# MAGI_sDIPBoard-2x.net
KiCad netlist of a schematic drawn in Altium Designer
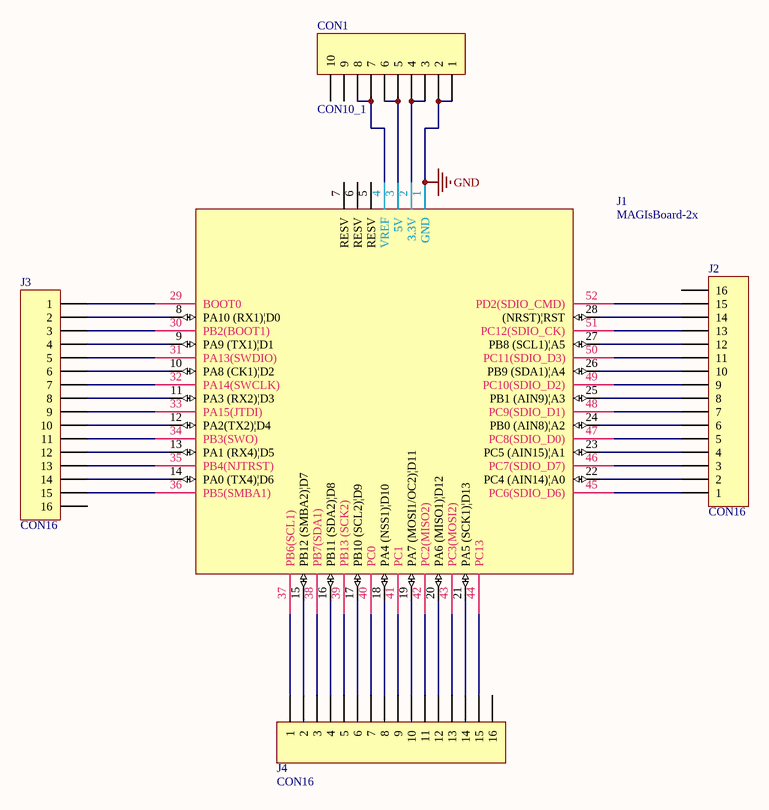
[diagram p0: MAGI'sDIPBoard-2x.SchDoc]

(export (version "E")
  (design (tool "Eeschema 10.0.6"))
  (components
    (comp (ref "CON1")
      (value "CON10_1")
      (footprint "idc10")
      (description "Connector")
      (libsource (lib "CON系列") (part "CON10_1"))
    )
    (comp (ref "J1")
      (value "MAGIsBoard-2x")
      (footprint "MAGIsBoard-2x")
      (libsource (lib "MAGIsBoard") (part "MAGIsBoard-2x"))
    )
    (comp (ref "J2")
      (value "CON16")
      (footprint "idc16")
      (description "Connector")
      (libsource (lib "") (part "CON16_2"))
    )
    (comp (ref "J3")
      (value "CON16")
      (footprint "idc16")
      (description "Connector")
      (libsource (lib "CON系列") (part "CON16"))
    )
    (comp (ref "J4")
      (value "CON16")
      (footprint "idc16")
      (description "Connector")
      (libsource (lib "") (part "CON16_1"))
    )
  )
  (nets
    (net (code "1") (name "GND") (class "Default")
      (node (ref "CON1") (pin "1") (pinfunction "1_1") (pintype "passive"))
      (node (ref "CON1") (pin "2") (pinfunction "2_2") (pintype "passive"))
      (node (ref "J1") (pin "1") (pinfunction "GND_1") (pintype "power_in"))
    )
    (net (code "2") (name "Net-(J1-(NRST)¦RST)") (class "Default")
      (node (ref "J1") (pin "28") (pinfunction "(NRST)¦RST_28") (pintype "bidirectional"))
      (node (ref "J2") (pin "14") (pinfunction "14_14") (pintype "passive"))
    )
    (net (code "3") (name "Net-(J1-3.3V)") (class "Default")
      (node (ref "CON1") (pin "3") (pinfunction "3_3") (pintype "passive"))
      (node (ref "CON1") (pin "4") (pinfunction "4_4") (pintype "passive"))
      (node (ref "J1") (pin "2") (pinfunction "3.3V_2") (pintype "power_in"))
    )
    (net (code "4") (name "Net-(J1-5V)") (class "Default")
      (node (ref "CON1") (pin "5") (pinfunction "5_5") (pintype "passive"))
      (node (ref "CON1") (pin "6") (pinfunction "6_6") (pintype "passive"))
      (node (ref "J1") (pin "3") (pinfunction "5V_3") (pintype "power_in"))
    )
    (net (code "5") (name "Net-(J1-BOOT0)") (class "Default")
      (node (ref "J1") (pin "29") (pinfunction "BOOT0_29") (pintype "passive"))
      (node (ref "J3") (pin "1") (pinfunction "1_1") (pintype "passive"))
    )
    (net (code "6") (name "Net-(J1-PA0_(TX4)¦D6)") (class "Default")
      (node (ref "J1") (pin "14") (pinfunction "PA0_(TX4)¦D6_14") (pintype "bidirectional"))
      (node (ref "J3") (pin "14") (pinfunction "14_14") (pintype "passive"))
    )
    (net (code "7") (name "Net-(J1-PA1_(RX4)¦D5)") (class "Default")
      (node (ref "J1") (pin "13") (pinfunction "PA1_(RX4)¦D5_13") (pintype "bidirectional"))
      (node (ref "J3") (pin "12") (pinfunction "12_12") (pintype "passive"))
    )
    (net (code "8") (name "Net-(J1-PA2(TX2)¦D4)") (class "Default")
      (node (ref "J1") (pin "12") (pinfunction "PA2(TX2)¦D4_12") (pintype "bidirectional"))
      (node (ref "J3") (pin "10") (pinfunction "10_10") (pintype "passive"))
    )
    (net (code "9") (name "Net-(J1-PA3_(RX2)¦D3)") (class "Default")
      (node (ref "J1") (pin "11") (pinfunction "PA3_(RX2)¦D3_11") (pintype "bidirectional"))
      (node (ref "J3") (pin "8") (pinfunction "8_8") (pintype "passive"))
    )
    (net (code "10") (name "Net-(J1-PA4_(NSS1)¦D10)") (class "Default")
      (node (ref "J1") (pin "18") (pinfunction "PA4_(NSS1)¦D10_18") (pintype "bidirectional"))
      (node (ref "J4") (pin "8") (pinfunction "8_8") (pintype "passive"))
    )
    (net (code "11") (name "Net-(J1-PA5_(SCK1)¦D13)") (class "Default")
      (node (ref "J1") (pin "21") (pinfunction "PA5_(SCK1)¦D13_21") (pintype "bidirectional"))
      (node (ref "J4") (pin "14") (pinfunction "14_14") (pintype "passive"))
    )
    (net (code "12") (name "Net-(J1-PA6_(MISO1)¦D12)") (class "Default")
      (node (ref "J1") (pin "20") (pinfunction "PA6_(MISO1)¦D12_20") (pintype "bidirectional"))
      (node (ref "J4") (pin "12") (pinfunction "12_12") (pintype "passive"))
    )
    (net (code "13") (name "Net-(J1-PA7_(MOSI1{slash}OC2)¦D11)") (class "Default")
      (node (ref "J1") (pin "19") (pinfunction "PA7_(MOSI1/OC2)¦D11_19") (pintype "bidirectional"))
      (node (ref "J4") (pin "10") (pinfunction "10_10") (pintype "passive"))
    )
    (net (code "14") (name "Net-(J1-PA8_(CK1)¦D2)") (class "Default")
      (node (ref "J1") (pin "10") (pinfunction "PA8_(CK1)¦D2_10") (pintype "bidirectional"))
      (node (ref "J3") (pin "6") (pinfunction "6_6") (pintype "passive"))
    )
    (net (code "15") (name "Net-(J1-PA9_(TX1)¦D1)") (class "Default")
      (node (ref "J1") (pin "9") (pinfunction "PA9_(TX1)¦D1_9") (pintype "bidirectional"))
      (node (ref "J3") (pin "4") (pinfunction "4_4") (pintype "passive"))
    )
    (net (code "16") (name "Net-(J1-PA10_(RX1)¦D0)") (class "Default")
      (node (ref "J1") (pin "8") (pinfunction "PA10_(RX1)¦D0_8") (pintype "bidirectional"))
      (node (ref "J3") (pin "2") (pinfunction "2_2") (pintype "passive"))
    )
    (net (code "17") (name "Net-(J1-PA13(SWDIO))") (class "Default")
      (node (ref "J1") (pin "31") (pinfunction "PA13(SWDIO)_31") (pintype "passive"))
      (node (ref "J3") (pin "5") (pinfunction "5_5") (pintype "passive"))
    )
    (net (code "18") (name "Net-(J1-PA14(SWCLK))") (class "Default")
      (node (ref "J1") (pin "32") (pinfunction "PA14(SWCLK)_32") (pintype "passive"))
      (node (ref "J3") (pin "7") (pinfunction "7_7") (pintype "passive"))
    )
    (net (code "19") (name "Net-(J1-PA15(JTDI))") (class "Default")
      (node (ref "J1") (pin "33") (pinfunction "PA15(JTDI)_33") (pintype "passive"))
      (node (ref "J3") (pin "9") (pinfunction "9_9") (pintype "passive"))
    )
    (net (code "20") (name "Net-(J1-PB0_(AIN8)¦A2)") (class "Default")
      (node (ref "J1") (pin "24") (pinfunction "PB0_(AIN8)¦A2_24") (pintype "bidirectional"))
      (node (ref "J2") (pin "6") (pinfunction "6_6") (pintype "passive"))
    )
    (net (code "21") (name "Net-(J1-PB1_(AIN9)¦A3)") (class "Default")
      (node (ref "J1") (pin "25") (pinfunction "PB1_(AIN9)¦A3_25") (pintype "bidirectional"))
      (node (ref "J2") (pin "8") (pinfunction "8_8") (pintype "passive"))
    )
    (net (code "22") (name "Net-(J1-PB2(BOOT1))") (class "Default")
      (node (ref "J1") (pin "30") (pinfunction "PB2(BOOT1)_30") (pintype "passive"))
      (node (ref "J3") (pin "3") (pinfunction "3_3") (pintype "passive"))
    )
    (net (code "23") (name "Net-(J1-PB3(SWO))") (class "Default")
      (node (ref "J1") (pin "34") (pinfunction "PB3(SWO)_34") (pintype "passive"))
      (node (ref "J3") (pin "11") (pinfunction "11_11") (pintype "passive"))
    )
    (net (code "24") (name "Net-(J1-PB4(NJTRST))") (class "Default")
      (node (ref "J1") (pin "35") (pinfunction "PB4(NJTRST)_35") (pintype "passive"))
      (node (ref "J3") (pin "13") (pinfunction "13_13") (pintype "passive"))
    )
    (net (code "25") (name "Net-(J1-PB5(SMBA1))") (class "Default")
      (node (ref "J1") (pin "36") (pinfunction "PB5(SMBA1)_36") (pintype "passive"))
      (node (ref "J3") (pin "15") (pinfunction "15_15") (pintype "passive"))
    )
    (net (code "26") (name "Net-(J1-PB6(SCL1))") (class "Default")
      (node (ref "J1") (pin "37") (pinfunction "PB6(SCL1)_37") (pintype "passive"))
      (node (ref "J4") (pin "1") (pinfunction "1_1") (pintype "passive"))
    )
    (net (code "27") (name "Net-(J1-PB7(SDA1))") (class "Default")
      (node (ref "J1") (pin "38") (pinfunction "PB7(SDA1)_38") (pintype "passive"))
      (node (ref "J4") (pin "3") (pinfunction "3_3") (pintype "passive"))
    )
    (net (code "28") (name "Net-(J1-PB8_(SCL1)¦A5)") (class "Default")
      (node (ref "J1") (pin "27") (pinfunction "PB8_(SCL1)¦A5_27") (pintype "bidirectional"))
      (node (ref "J2") (pin "12") (pinfunction "12_12") (pintype "passive"))
    )
    (net (code "29") (name "Net-(J1-PB9_(SDA1)¦A4)") (class "Default")
      (node (ref "J1") (pin "26") (pinfunction "PB9_(SDA1)¦A4_26") (pintype "bidirectional"))
      (node (ref "J2") (pin "10") (pinfunction "10_10") (pintype "passive"))
    )
    (net (code "30") (name "Net-(J1-PB10_(SCL2)¦D9)") (class "Default")
      (node (ref "J1") (pin "17") (pinfunction "PB10_(SCL2)¦D9_17") (pintype "bidirectional"))
      (node (ref "J4") (pin "6") (pinfunction "6_6") (pintype "passive"))
    )
    (net (code "31") (name "Net-(J1-PB11_(SDA2)¦D8)") (class "Default")
      (node (ref "J1") (pin "16") (pinfunction "PB11_(SDA2)¦D8_16") (pintype "bidirectional"))
      (node (ref "J4") (pin "4") (pinfunction "4_4") (pintype "passive"))
    )
    (net (code "32") (name "Net-(J1-PB12_(SMBA2)¦D7)") (class "Default")
      (node (ref "J1") (pin "15") (pinfunction "PB12_(SMBA2)¦D7_15") (pintype "bidirectional"))
      (node (ref "J4") (pin "2") (pinfunction "2_2") (pintype "passive"))
    )
    (net (code "33") (name "Net-(J1-PB13_(SCK2))") (class "Default")
      (node (ref "J1") (pin "39") (pinfunction "PB13_(SCK2)_39") (pintype "passive"))
      (node (ref "J4") (pin "5") (pinfunction "5_5") (pintype "passive"))
    )
    (net (code "34") (name "Net-(J1-PC0)") (class "Default")
      (node (ref "J1") (pin "40") (pinfunction "PC0_40") (pintype "passive"))
      (node (ref "J4") (pin "7") (pinfunction "7_7") (pintype "passive"))
    )
    (net (code "35") (name "Net-(J1-PC1)") (class "Default")
      (node (ref "J1") (pin "41") (pinfunction "PC1_41") (pintype "passive"))
      (node (ref "J4") (pin "9") (pinfunction "9_9") (pintype "passive"))
    )
    (net (code "36") (name "Net-(J1-PC2(MISO2))") (class "Default")
      (node (ref "J1") (pin "42") (pinfunction "PC2(MISO2)_42") (pintype "passive"))
      (node (ref "J4") (pin "11") (pinfunction "11_11") (pintype "passive"))
    )
    (net (code "37") (name "Net-(J1-PC3(MOSI2))") (class "Default")
      (node (ref "J1") (pin "43") (pinfunction "PC3(MOSI2)_43") (pintype "passive"))
      (node (ref "J4") (pin "13") (pinfunction "13_13") (pintype "passive"))
    )
    (net (code "38") (name "Net-(J1-PC4_(AIN14)¦A0)") (class "Default")
      (node (ref "J1") (pin "22") (pinfunction "PC4_(AIN14)¦A0_22") (pintype "bidirectional"))
      (node (ref "J2") (pin "2") (pinfunction "2_2") (pintype "passive"))
    )
    (net (code "39") (name "Net-(J1-PC5_(AIN15)¦A1)") (class "Default")
      (node (ref "J1") (pin "23") (pinfunction "PC5_(AIN15)¦A1_23") (pintype "bidirectional"))
      (node (ref "J2") (pin "4") (pinfunction "4_4") (pintype "passive"))
    )
    (net (code "40") (name "Net-(J1-PC6(SDIO_D6))") (class "Default")
      (node (ref "J1") (pin "45") (pinfunction "PC6(SDIO_D6)_45") (pintype "passive"))
      (node (ref "J2") (pin "1") (pinfunction "1_1") (pintype "passive"))
    )
    (net (code "41") (name "Net-(J1-PC7(SDIO_D7))") (class "Default")
      (node (ref "J1") (pin "46") (pinfunction "PC7(SDIO_D7)_46") (pintype "passive"))
      (node (ref "J2") (pin "3") (pinfunction "3_3") (pintype "passive"))
    )
    (net (code "42") (name "Net-(J1-PC8(SDIO_D0))") (class "Default")
      (node (ref "J1") (pin "47") (pinfunction "PC8(SDIO_D0)_47") (pintype "passive"))
      (node (ref "J2") (pin "5") (pinfunction "5_5") (pintype "passive"))
    )
    (net (code "43") (name "Net-(J1-PC9(SDIO_D1))") (class "Default")
      (node (ref "J1") (pin "48") (pinfunction "PC9(SDIO_D1)_48") (pintype "passive"))
      (node (ref "J2") (pin "7") (pinfunction "7_7") (pintype "passive"))
    )
    (net (code "44") (name "Net-(J1-PC10(SDIO_D2))") (class "Default")
      (node (ref "J1") (pin "49") (pinfunction "PC10(SDIO_D2)_49") (pintype "passive"))
      (node (ref "J2") (pin "9") (pinfunction "9_9") (pintype "passive"))
    )
    (net (code "45") (name "Net-(J1-PC11(SDIO_D3))") (class "Default")
      (node (ref "J1") (pin "50") (pinfunction "PC11(SDIO_D3)_50") (pintype "passive"))
      (node (ref "J2") (pin "11") (pinfunction "11_11") (pintype "passive"))
    )
    (net (code "46") (name "Net-(J1-PC12(SDIO_CK))") (class "Default")
      (node (ref "J1") (pin "51") (pinfunction "PC12(SDIO_CK)_51") (pintype "passive"))
      (node (ref "J2") (pin "13") (pinfunction "13_13") (pintype "passive"))
    )
    (net (code "47") (name "Net-(J1-PC13)") (class "Default")
      (node (ref "J1") (pin "44") (pinfunction "PC13_44") (pintype "passive"))
      (node (ref "J4") (pin "15") (pinfunction "15_15") (pintype "passive"))
    )
    (net (code "48") (name "Net-(J1-PD2(SDIO_CMD))") (class "Default")
      (node (ref "J1") (pin "52") (pinfunction "PD2(SDIO_CMD)_52") (pintype "passive"))
      (node (ref "J2") (pin "15") (pinfunction "15_15") (pintype "passive"))
    )
    (net (code "49") (name "Net-(J1-VREF)") (class "Default")
      (node (ref "CON1") (pin "7") (pinfunction "7_7") (pintype "passive"))
      (node (ref "CON1") (pin "8") (pinfunction "8_8") (pintype "passive"))
      (node (ref "J1") (pin "4") (pinfunction "VREF_4") (pintype "passive"))
    )
    (net (code "50") (name "unconnected-(CON1-Pad9)") (class "Default")
      (node (ref "CON1") (pin "9") (pinfunction "9_9") (pintype "passive"))
    )
    (net (code "51") (name "unconnected-(CON1-Pad10)") (class "Default")
      (node (ref "CON1") (pin "10") (pinfunction "10_10") (pintype "passive"))
    )
    (net (code "52") (name "unconnected-(J1-RESV-Pad5)") (class "Default")
      (node (ref "J1") (pin "5") (pinfunction "RESV_5") (pintype "passive"))
    )
    (net (code "53") (name "unconnected-(J1-RESV-Pad6)") (class "Default")
      (node (ref "J1") (pin "6") (pinfunction "RESV_6") (pintype "passive"))
    )
    (net (code "54") (name "unconnected-(J1-RESV-Pad7)") (class "Default")
      (node (ref "J1") (pin "7") (pinfunction "RESV_7") (pintype "passive"))
    )
    (net (code "55") (name "unconnected-(J2-Pad16)") (class "Default")
      (node (ref "J2") (pin "16") (pinfunction "16_16") (pintype "passive"))
    )
    (net (code "56") (name "unconnected-(J3-Pad16)") (class "Default")
      (node (ref "J3") (pin "16") (pinfunction "16_16") (pintype "passive"))
    )
    (net (code "57") (name "unconnected-(J4-Pad16)") (class "Default")
      (node (ref "J4") (pin "16") (pinfunction "16_16") (pintype "passive"))
    )
  )
)
